# Choin_led1_0.net
KiCad netlist of a schematic drawn in Altium Designer
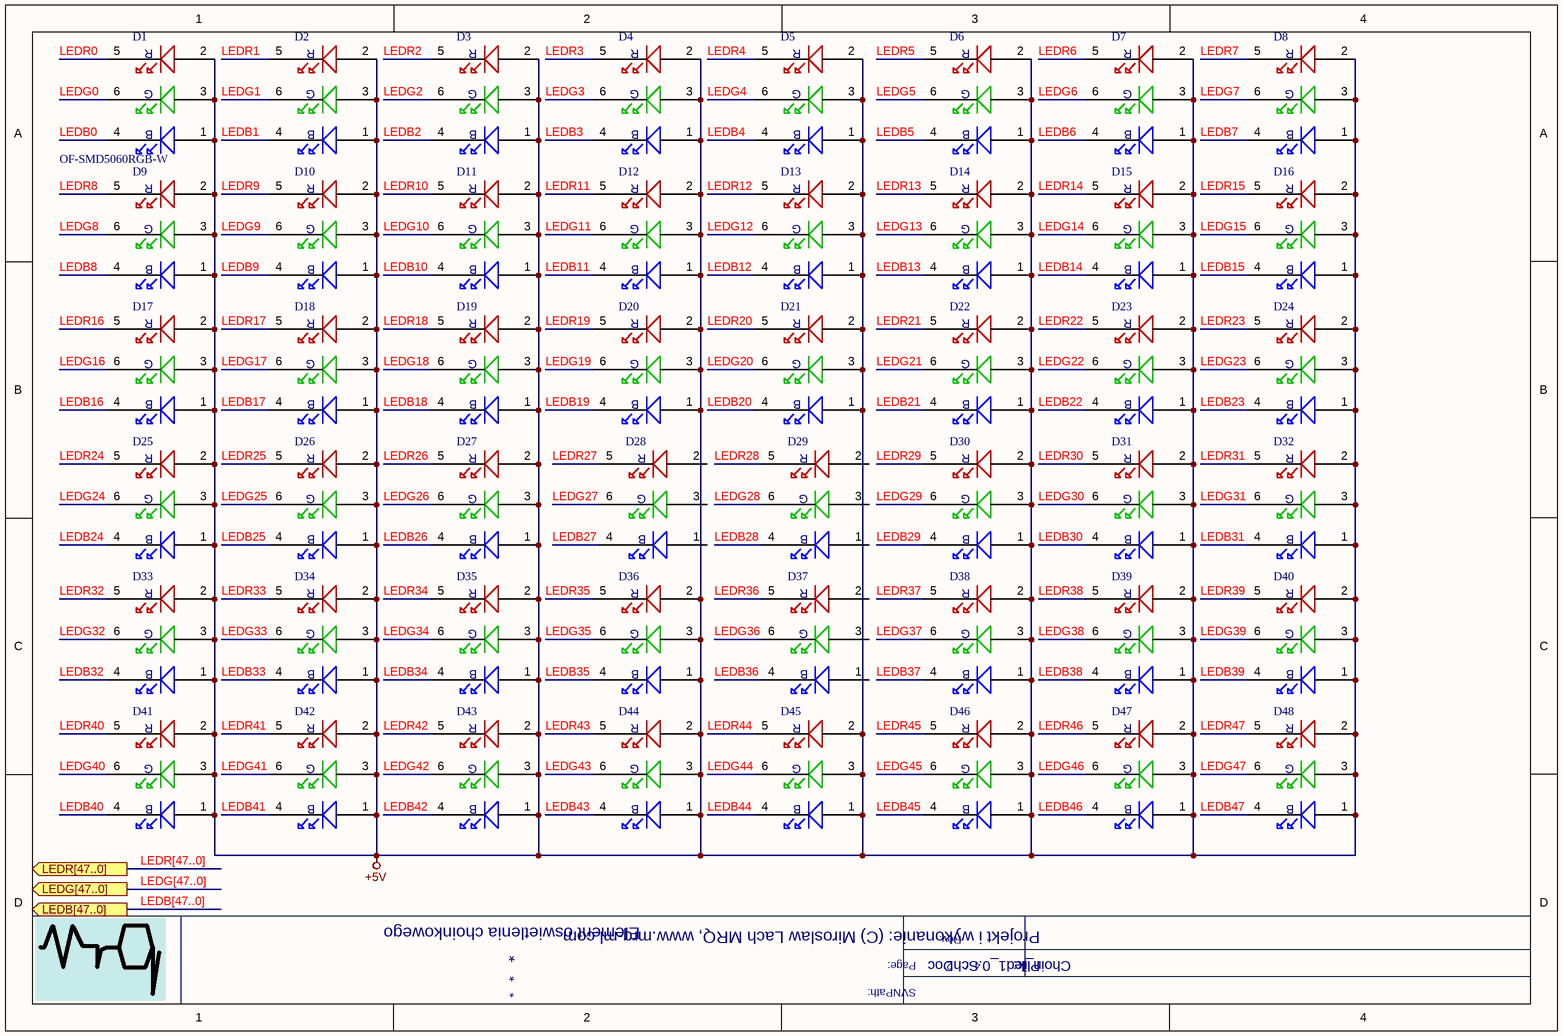
[diagram p0: Choin_led1_0.SchDoc]

(export (version "E")
  (design (tool "Eeschema 10.0.6"))
  (components
    (comp (ref "D1")
      (value "OF-SMD5060RGB-W")
      (footprint "OF-SMD5060RGB-W")
      (libsource (lib "Parts") (part "OF-SMD5060RGB-W"))
    )
    (comp (ref "D2")
      (value "OF-SMD5060RGB-W")
      (footprint "OF-SMD5060RGB-W")
      (libsource (lib "Parts") (part "OF-SMD5060RGB-W"))
    )
    (comp (ref "D3")
      (value "OF-SMD5060RGB-W")
      (footprint "OF-SMD5060RGB-W")
      (libsource (lib "Parts") (part "OF-SMD5060RGB-W"))
    )
    (comp (ref "D4")
      (value "OF-SMD5060RGB-W")
      (footprint "OF-SMD5060RGB-W")
      (libsource (lib "Parts") (part "OF-SMD5060RGB-W"))
    )
    (comp (ref "D5")
      (value "OF-SMD5060RGB-W")
      (footprint "OF-SMD5060RGB-W")
      (libsource (lib "Parts") (part "OF-SMD5060RGB-W"))
    )
    (comp (ref "D6")
      (value "OF-SMD5060RGB-W")
      (footprint "OF-SMD5060RGB-W")
      (libsource (lib "Parts") (part "OF-SMD5060RGB-W"))
    )
    (comp (ref "D7")
      (value "OF-SMD5060RGB-W")
      (footprint "OF-SMD5060RGB-W")
      (libsource (lib "Parts") (part "OF-SMD5060RGB-W"))
    )
    (comp (ref "D8")
      (value "OF-SMD5060RGB-W")
      (footprint "OF-SMD5060RGB-W")
      (libsource (lib "Parts") (part "OF-SMD5060RGB-W"))
    )
    (comp (ref "D9")
      (value "OF-SMD5060RGB-W")
      (footprint "OF-SMD5060RGB-W")
      (libsource (lib "Parts") (part "OF-SMD5060RGB-W"))
    )
    (comp (ref "D10")
      (value "OF-SMD5060RGB-W")
      (footprint "OF-SMD5060RGB-W")
      (libsource (lib "Parts") (part "OF-SMD5060RGB-W"))
    )
    (comp (ref "D11")
      (value "OF-SMD5060RGB-W")
      (footprint "OF-SMD5060RGB-W")
      (libsource (lib "Parts") (part "OF-SMD5060RGB-W"))
    )
    (comp (ref "D12")
      (value "OF-SMD5060RGB-W")
      (footprint "OF-SMD5060RGB-W")
      (libsource (lib "Parts") (part "OF-SMD5060RGB-W"))
    )
    (comp (ref "D13")
      (value "OF-SMD5060RGB-W")
      (footprint "OF-SMD5060RGB-W")
      (libsource (lib "Parts") (part "OF-SMD5060RGB-W"))
    )
    (comp (ref "D14")
      (value "OF-SMD5060RGB-W")
      (footprint "OF-SMD5060RGB-W")
      (libsource (lib "Parts") (part "OF-SMD5060RGB-W"))
    )
    (comp (ref "D15")
      (value "OF-SMD5060RGB-W")
      (footprint "OF-SMD5060RGB-W")
      (libsource (lib "Parts") (part "OF-SMD5060RGB-W"))
    )
    (comp (ref "D16")
      (value "OF-SMD5060RGB-W")
      (footprint "OF-SMD5060RGB-W")
      (libsource (lib "Parts") (part "OF-SMD5060RGB-W"))
    )
    (comp (ref "D17")
      (value "OF-SMD5060RGB-W")
      (footprint "OF-SMD5060RGB-W")
      (libsource (lib "Parts") (part "OF-SMD5060RGB-W"))
    )
    (comp (ref "D18")
      (value "OF-SMD5060RGB-W")
      (footprint "OF-SMD5060RGB-W")
      (libsource (lib "Parts") (part "OF-SMD5060RGB-W"))
    )
    (comp (ref "D19")
      (value "OF-SMD5060RGB-W")
      (footprint "OF-SMD5060RGB-W")
      (libsource (lib "Parts") (part "OF-SMD5060RGB-W"))
    )
    (comp (ref "D20")
      (value "OF-SMD5060RGB-W")
      (footprint "OF-SMD5060RGB-W")
      (libsource (lib "Parts") (part "OF-SMD5060RGB-W"))
    )
    (comp (ref "D21")
      (value "OF-SMD5060RGB-W")
      (footprint "OF-SMD5060RGB-W")
      (libsource (lib "Parts") (part "OF-SMD5060RGB-W"))
    )
    (comp (ref "D22")
      (value "OF-SMD5060RGB-W")
      (footprint "OF-SMD5060RGB-W")
      (libsource (lib "Parts") (part "OF-SMD5060RGB-W"))
    )
    (comp (ref "D23")
      (value "OF-SMD5060RGB-W")
      (footprint "OF-SMD5060RGB-W")
      (libsource (lib "Parts") (part "OF-SMD5060RGB-W"))
    )
    (comp (ref "D24")
      (value "OF-SMD5060RGB-W")
      (footprint "OF-SMD5060RGB-W")
      (libsource (lib "Parts") (part "OF-SMD5060RGB-W"))
    )
    (comp (ref "D25")
      (value "OF-SMD5060RGB-W")
      (footprint "OF-SMD5060RGB-W")
      (libsource (lib "Parts") (part "OF-SMD5060RGB-W"))
    )
    (comp (ref "D26")
      (value "OF-SMD5060RGB-W")
      (footprint "OF-SMD5060RGB-W")
      (libsource (lib "Parts") (part "OF-SMD5060RGB-W"))
    )
    (comp (ref "D27")
      (value "OF-SMD5060RGB-W")
      (footprint "OF-SMD5060RGB-W")
      (libsource (lib "Parts") (part "OF-SMD5060RGB-W"))
    )
    (comp (ref "D28")
      (value "OF-SMD5060RGB-W")
      (footprint "OF-SMD5060RGB-W")
      (libsource (lib "Parts") (part "OF-SMD5060RGB-W"))
    )
    (comp (ref "D29")
      (value "OF-SMD5060RGB-W")
      (footprint "OF-SMD5060RGB-W")
      (libsource (lib "Parts") (part "OF-SMD5060RGB-W"))
    )
    (comp (ref "D30")
      (value "OF-SMD5060RGB-W")
      (footprint "OF-SMD5060RGB-W")
      (libsource (lib "Parts") (part "OF-SMD5060RGB-W"))
    )
    (comp (ref "D31")
      (value "OF-SMD5060RGB-W")
      (footprint "OF-SMD5060RGB-W")
      (libsource (lib "Parts") (part "OF-SMD5060RGB-W"))
    )
    (comp (ref "D32")
      (value "OF-SMD5060RGB-W")
      (footprint "OF-SMD5060RGB-W")
      (libsource (lib "Parts") (part "OF-SMD5060RGB-W"))
    )
    (comp (ref "D33")
      (value "OF-SMD5060RGB-W")
      (footprint "OF-SMD5060RGB-W")
      (libsource (lib "Parts") (part "OF-SMD5060RGB-W"))
    )
    (comp (ref "D34")
      (value "OF-SMD5060RGB-W")
      (footprint "OF-SMD5060RGB-W")
      (libsource (lib "Parts") (part "OF-SMD5060RGB-W"))
    )
    (comp (ref "D35")
      (value "OF-SMD5060RGB-W")
      (footprint "OF-SMD5060RGB-W")
      (libsource (lib "Parts") (part "OF-SMD5060RGB-W"))
    )
    (comp (ref "D36")
      (value "OF-SMD5060RGB-W")
      (footprint "OF-SMD5060RGB-W")
      (libsource (lib "Parts") (part "OF-SMD5060RGB-W"))
    )
    (comp (ref "D37")
      (value "OF-SMD5060RGB-W")
      (footprint "OF-SMD5060RGB-W")
      (libsource (lib "Parts") (part "OF-SMD5060RGB-W"))
    )
    (comp (ref "D38")
      (value "OF-SMD5060RGB-W")
      (footprint "OF-SMD5060RGB-W")
      (libsource (lib "Parts") (part "OF-SMD5060RGB-W"))
    )
    (comp (ref "D39")
      (value "OF-SMD5060RGB-W")
      (footprint "OF-SMD5060RGB-W")
      (libsource (lib "Parts") (part "OF-SMD5060RGB-W"))
    )
    (comp (ref "D40")
      (value "OF-SMD5060RGB-W")
      (footprint "OF-SMD5060RGB-W")
      (libsource (lib "Parts") (part "OF-SMD5060RGB-W"))
    )
    (comp (ref "D41")
      (value "OF-SMD5060RGB-W")
      (footprint "OF-SMD5060RGB-W")
      (libsource (lib "Parts") (part "OF-SMD5060RGB-W"))
    )
    (comp (ref "D42")
      (value "OF-SMD5060RGB-W")
      (footprint "OF-SMD5060RGB-W")
      (libsource (lib "Parts") (part "OF-SMD5060RGB-W"))
    )
    (comp (ref "D43")
      (value "OF-SMD5060RGB-W")
      (footprint "OF-SMD5060RGB-W")
      (libsource (lib "Parts") (part "OF-SMD5060RGB-W"))
    )
    (comp (ref "D44")
      (value "OF-SMD5060RGB-W")
      (footprint "OF-SMD5060RGB-W")
      (libsource (lib "Parts") (part "OF-SMD5060RGB-W"))
    )
    (comp (ref "D45")
      (value "OF-SMD5060RGB-W")
      (footprint "OF-SMD5060RGB-W")
      (libsource (lib "Parts") (part "OF-SMD5060RGB-W"))
    )
    (comp (ref "D46")
      (value "OF-SMD5060RGB-W")
      (footprint "OF-SMD5060RGB-W")
      (libsource (lib "Parts") (part "OF-SMD5060RGB-W"))
    )
    (comp (ref "D47")
      (value "OF-SMD5060RGB-W")
      (footprint "OF-SMD5060RGB-W")
      (libsource (lib "Parts") (part "OF-SMD5060RGB-W"))
    )
    (comp (ref "D48")
      (value "OF-SMD5060RGB-W")
      (footprint "OF-SMD5060RGB-W")
      (libsource (lib "Parts") (part "OF-SMD5060RGB-W"))
    )
  )
  (nets
    (net (code "1") (name "+5V") (class "Default")
      (node (ref "D1") (pin "1") (pinfunction "ANOD_1") (pintype "passive"))
      (node (ref "D1") (pin "2") (pinfunction "ANOD_2") (pintype "passive"))
      (node (ref "D1") (pin "3") (pinfunction "ANOD_3") (pintype "passive"))
      (node (ref "D10") (pin "1") (pinfunction "ANOD_1") (pintype "passive"))
      (node (ref "D10") (pin "2") (pinfunction "ANOD_2") (pintype "passive"))
      (node (ref "D10") (pin "3") (pinfunction "ANOD_3") (pintype "passive"))
      (node (ref "D11") (pin "1") (pinfunction "ANOD_1") (pintype "passive"))
      (node (ref "D11") (pin "2") (pinfunction "ANOD_2") (pintype "passive"))
      (node (ref "D11") (pin "3") (pinfunction "ANOD_3") (pintype "passive"))
      (node (ref "D12") (pin "1") (pinfunction "ANOD_1") (pintype "passive"))
      (node (ref "D12") (pin "2") (pinfunction "ANOD_2") (pintype "passive"))
      (node (ref "D12") (pin "3") (pinfunction "ANOD_3") (pintype "passive"))
      (node (ref "D13") (pin "1") (pinfunction "ANOD_1") (pintype "passive"))
      (node (ref "D13") (pin "2") (pinfunction "ANOD_2") (pintype "passive"))
      (node (ref "D13") (pin "3") (pinfunction "ANOD_3") (pintype "passive"))
      (node (ref "D14") (pin "1") (pinfunction "ANOD_1") (pintype "passive"))
      (node (ref "D14") (pin "2") (pinfunction "ANOD_2") (pintype "passive"))
      (node (ref "D14") (pin "3") (pinfunction "ANOD_3") (pintype "passive"))
      (node (ref "D15") (pin "1") (pinfunction "ANOD_1") (pintype "passive"))
      (node (ref "D15") (pin "2") (pinfunction "ANOD_2") (pintype "passive"))
      (node (ref "D15") (pin "3") (pinfunction "ANOD_3") (pintype "passive"))
      (node (ref "D16") (pin "1") (pinfunction "ANOD_1") (pintype "passive"))
      (node (ref "D16") (pin "2") (pinfunction "ANOD_2") (pintype "passive"))
      (node (ref "D16") (pin "3") (pinfunction "ANOD_3") (pintype "passive"))
      (node (ref "D17") (pin "1") (pinfunction "ANOD_1") (pintype "passive"))
      (node (ref "D17") (pin "2") (pinfunction "ANOD_2") (pintype "passive"))
      (node (ref "D17") (pin "3") (pinfunction "ANOD_3") (pintype "passive"))
      (node (ref "D18") (pin "1") (pinfunction "ANOD_1") (pintype "passive"))
      (node (ref "D18") (pin "2") (pinfunction "ANOD_2") (pintype "passive"))
      (node (ref "D18") (pin "3") (pinfunction "ANOD_3") (pintype "passive"))
      (node (ref "D19") (pin "1") (pinfunction "ANOD_1") (pintype "passive"))
      (node (ref "D19") (pin "2") (pinfunction "ANOD_2") (pintype "passive"))
      (node (ref "D19") (pin "3") (pinfunction "ANOD_3") (pintype "passive"))
      (node (ref "D2") (pin "1") (pinfunction "ANOD_1") (pintype "passive"))
      (node (ref "D2") (pin "2") (pinfunction "ANOD_2") (pintype "passive"))
      (node (ref "D2") (pin "3") (pinfunction "ANOD_3") (pintype "passive"))
      (node (ref "D20") (pin "1") (pinfunction "ANOD_1") (pintype "passive"))
      (node (ref "D20") (pin "2") (pinfunction "ANOD_2") (pintype "passive"))
      (node (ref "D20") (pin "3") (pinfunction "ANOD_3") (pintype "passive"))
      (node (ref "D21") (pin "1") (pinfunction "ANOD_1") (pintype "passive"))
      (node (ref "D21") (pin "2") (pinfunction "ANOD_2") (pintype "passive"))
      (node (ref "D21") (pin "3") (pinfunction "ANOD_3") (pintype "passive"))
      (node (ref "D22") (pin "1") (pinfunction "ANOD_1") (pintype "passive"))
      (node (ref "D22") (pin "2") (pinfunction "ANOD_2") (pintype "passive"))
      (node (ref "D22") (pin "3") (pinfunction "ANOD_3") (pintype "passive"))
      (node (ref "D23") (pin "1") (pinfunction "ANOD_1") (pintype "passive"))
      (node (ref "D23") (pin "2") (pinfunction "ANOD_2") (pintype "passive"))
      (node (ref "D23") (pin "3") (pinfunction "ANOD_3") (pintype "passive"))
      (node (ref "D24") (pin "1") (pinfunction "ANOD_1") (pintype "passive"))
      (node (ref "D24") (pin "2") (pinfunction "ANOD_2") (pintype "passive"))
      (node (ref "D24") (pin "3") (pinfunction "ANOD_3") (pintype "passive"))
      (node (ref "D25") (pin "1") (pinfunction "ANOD_1") (pintype "passive"))
      (node (ref "D25") (pin "2") (pinfunction "ANOD_2") (pintype "passive"))
      (node (ref "D25") (pin "3") (pinfunction "ANOD_3") (pintype "passive"))
      (node (ref "D26") (pin "1") (pinfunction "ANOD_1") (pintype "passive"))
      (node (ref "D26") (pin "2") (pinfunction "ANOD_2") (pintype "passive"))
      (node (ref "D26") (pin "3") (pinfunction "ANOD_3") (pintype "passive"))
      (node (ref "D27") (pin "1") (pinfunction "ANOD_1") (pintype "passive"))
      (node (ref "D27") (pin "2") (pinfunction "ANOD_2") (pintype "passive"))
      (node (ref "D27") (pin "3") (pinfunction "ANOD_3") (pintype "passive"))
      (node (ref "D3") (pin "1") (pinfunction "ANOD_1") (pintype "passive"))
      (node (ref "D3") (pin "2") (pinfunction "ANOD_2") (pintype "passive"))
      (node (ref "D3") (pin "3") (pinfunction "ANOD_3") (pintype "passive"))
      (node (ref "D30") (pin "1") (pinfunction "ANOD_1") (pintype "passive"))
      (node (ref "D30") (pin "2") (pinfunction "ANOD_2") (pintype "passive"))
      (node (ref "D30") (pin "3") (pinfunction "ANOD_3") (pintype "passive"))
      (node (ref "D31") (pin "1") (pinfunction "ANOD_1") (pintype "passive"))
      (node (ref "D31") (pin "2") (pinfunction "ANOD_2") (pintype "passive"))
      (node (ref "D31") (pin "3") (pinfunction "ANOD_3") (pintype "passive"))
      (node (ref "D32") (pin "1") (pinfunction "ANOD_1") (pintype "passive"))
      (node (ref "D32") (pin "2") (pinfunction "ANOD_2") (pintype "passive"))
      (node (ref "D32") (pin "3") (pinfunction "ANOD_3") (pintype "passive"))
      (node (ref "D33") (pin "1") (pinfunction "ANOD_1") (pintype "passive"))
      (node (ref "D33") (pin "2") (pinfunction "ANOD_2") (pintype "passive"))
      (node (ref "D33") (pin "3") (pinfunction "ANOD_3") (pintype "passive"))
      (node (ref "D34") (pin "1") (pinfunction "ANOD_1") (pintype "passive"))
      (node (ref "D34") (pin "2") (pinfunction "ANOD_2") (pintype "passive"))
      (node (ref "D34") (pin "3") (pinfunction "ANOD_3") (pintype "passive"))
      (node (ref "D35") (pin "1") (pinfunction "ANOD_1") (pintype "passive"))
      (node (ref "D35") (pin "2") (pinfunction "ANOD_2") (pintype "passive"))
      (node (ref "D35") (pin "3") (pinfunction "ANOD_3") (pintype "passive"))
      (node (ref "D36") (pin "1") (pinfunction "ANOD_1") (pintype "passive"))
      (node (ref "D36") (pin "2") (pinfunction "ANOD_2") (pintype "passive"))
      (node (ref "D36") (pin "3") (pinfunction "ANOD_3") (pintype "passive"))
      (node (ref "D38") (pin "1") (pinfunction "ANOD_1") (pintype "passive"))
      (node (ref "D38") (pin "2") (pinfunction "ANOD_2") (pintype "passive"))
      (node (ref "D38") (pin "3") (pinfunction "ANOD_3") (pintype "passive"))
      (node (ref "D39") (pin "1") (pinfunction "ANOD_1") (pintype "passive"))
      (node (ref "D39") (pin "2") (pinfunction "ANOD_2") (pintype "passive"))
      (node (ref "D39") (pin "3") (pinfunction "ANOD_3") (pintype "passive"))
      (node (ref "D4") (pin "1") (pinfunction "ANOD_1") (pintype "passive"))
      (node (ref "D4") (pin "2") (pinfunction "ANOD_2") (pintype "passive"))
      (node (ref "D4") (pin "3") (pinfunction "ANOD_3") (pintype "passive"))
      (node (ref "D40") (pin "1") (pinfunction "ANOD_1") (pintype "passive"))
      (node (ref "D40") (pin "2") (pinfunction "ANOD_2") (pintype "passive"))
      (node (ref "D40") (pin "3") (pinfunction "ANOD_3") (pintype "passive"))
      (node (ref "D41") (pin "1") (pinfunction "ANOD_1") (pintype "passive"))
      (node (ref "D41") (pin "2") (pinfunction "ANOD_2") (pintype "passive"))
      (node (ref "D41") (pin "3") (pinfunction "ANOD_3") (pintype "passive"))
      (node (ref "D42") (pin "1") (pinfunction "ANOD_1") (pintype "passive"))
      (node (ref "D42") (pin "2") (pinfunction "ANOD_2") (pintype "passive"))
      (node (ref "D42") (pin "3") (pinfunction "ANOD_3") (pintype "passive"))
      (node (ref "D43") (pin "1") (pinfunction "ANOD_1") (pintype "passive"))
      (node (ref "D43") (pin "2") (pinfunction "ANOD_2") (pintype "passive"))
      (node (ref "D43") (pin "3") (pinfunction "ANOD_3") (pintype "passive"))
      (node (ref "D44") (pin "1") (pinfunction "ANOD_1") (pintype "passive"))
      (node (ref "D44") (pin "2") (pinfunction "ANOD_2") (pintype "passive"))
      (node (ref "D44") (pin "3") (pinfunction "ANOD_3") (pintype "passive"))
      (node (ref "D45") (pin "1") (pinfunction "ANOD_1") (pintype "passive"))
      (node (ref "D45") (pin "2") (pinfunction "ANOD_2") (pintype "passive"))
      (node (ref "D45") (pin "3") (pinfunction "ANOD_3") (pintype "passive"))
      (node (ref "D46") (pin "1") (pinfunction "ANOD_1") (pintype "passive"))
      (node (ref "D46") (pin "2") (pinfunction "ANOD_2") (pintype "passive"))
      (node (ref "D46") (pin "3") (pinfunction "ANOD_3") (pintype "passive"))
      (node (ref "D47") (pin "1") (pinfunction "ANOD_1") (pintype "passive"))
      (node (ref "D47") (pin "2") (pinfunction "ANOD_2") (pintype "passive"))
      (node (ref "D47") (pin "3") (pinfunction "ANOD_3") (pintype "passive"))
      (node (ref "D48") (pin "1") (pinfunction "ANOD_1") (pintype "passive"))
      (node (ref "D48") (pin "2") (pinfunction "ANOD_2") (pintype "passive"))
      (node (ref "D48") (pin "3") (pinfunction "ANOD_3") (pintype "passive"))
      (node (ref "D5") (pin "1") (pinfunction "ANOD_1") (pintype "passive"))
      (node (ref "D5") (pin "2") (pinfunction "ANOD_2") (pintype "passive"))
      (node (ref "D5") (pin "3") (pinfunction "ANOD_3") (pintype "passive"))
      (node (ref "D6") (pin "1") (pinfunction "ANOD_1") (pintype "passive"))
      (node (ref "D6") (pin "2") (pinfunction "ANOD_2") (pintype "passive"))
      (node (ref "D6") (pin "3") (pinfunction "ANOD_3") (pintype "passive"))
      (node (ref "D7") (pin "1") (pinfunction "ANOD_1") (pintype "passive"))
      (node (ref "D7") (pin "2") (pinfunction "ANOD_2") (pintype "passive"))
      (node (ref "D7") (pin "3") (pinfunction "ANOD_3") (pintype "passive"))
      (node (ref "D8") (pin "1") (pinfunction "ANOD_1") (pintype "passive"))
      (node (ref "D8") (pin "2") (pinfunction "ANOD_2") (pintype "passive"))
      (node (ref "D8") (pin "3") (pinfunction "ANOD_3") (pintype "passive"))
      (node (ref "D9") (pin "1") (pinfunction "ANOD_1") (pintype "passive"))
      (node (ref "D9") (pin "2") (pinfunction "ANOD_2") (pintype "passive"))
      (node (ref "D9") (pin "3") (pinfunction "ANOD_3") (pintype "passive"))
    )
    (net (code "2") (name "/LEDB0") (class "Default")
      (node (ref "D1") (pin "4") (pinfunction "CATH_4") (pintype "passive"))
    )
    (net (code "3") (name "/LEDB1") (class "Default")
      (node (ref "D2") (pin "4") (pinfunction "CATH_4") (pintype "passive"))
    )
    (net (code "4") (name "/LEDB2") (class "Default")
      (node (ref "D3") (pin "4") (pinfunction "CATH_4") (pintype "passive"))
    )
    (net (code "5") (name "/LEDB3") (class "Default")
      (node (ref "D4") (pin "4") (pinfunction "CATH_4") (pintype "passive"))
    )
    (net (code "6") (name "/LEDB4") (class "Default")
      (node (ref "D5") (pin "4") (pinfunction "CATH_4") (pintype "passive"))
    )
    (net (code "7") (name "/LEDB5") (class "Default")
      (node (ref "D6") (pin "4") (pinfunction "CATH_4") (pintype "passive"))
    )
    (net (code "8") (name "/LEDB6") (class "Default")
      (node (ref "D7") (pin "4") (pinfunction "CATH_4") (pintype "passive"))
    )
    (net (code "9") (name "/LEDB7") (class "Default")
      (node (ref "D8") (pin "4") (pinfunction "CATH_4") (pintype "passive"))
    )
    (net (code "10") (name "/LEDB8") (class "Default")
      (node (ref "D9") (pin "4") (pinfunction "CATH_4") (pintype "passive"))
    )
    (net (code "11") (name "/LEDB9") (class "Default")
      (node (ref "D10") (pin "4") (pinfunction "CATH_4") (pintype "passive"))
    )
    (net (code "12") (name "/LEDB10") (class "Default")
      (node (ref "D11") (pin "4") (pinfunction "CATH_4") (pintype "passive"))
    )
    (net (code "13") (name "/LEDB11") (class "Default")
      (node (ref "D12") (pin "4") (pinfunction "CATH_4") (pintype "passive"))
    )
    (net (code "14") (name "/LEDB12") (class "Default")
      (node (ref "D13") (pin "4") (pinfunction "CATH_4") (pintype "passive"))
    )
    (net (code "15") (name "/LEDB13") (class "Default")
      (node (ref "D14") (pin "4") (pinfunction "CATH_4") (pintype "passive"))
    )
    (net (code "16") (name "/LEDB14") (class "Default")
      (node (ref "D15") (pin "4") (pinfunction "CATH_4") (pintype "passive"))
    )
    (net (code "17") (name "/LEDB15") (class "Default")
      (node (ref "D16") (pin "4") (pinfunction "CATH_4") (pintype "passive"))
    )
    (net (code "18") (name "/LEDB16") (class "Default")
      (node (ref "D17") (pin "4") (pinfunction "CATH_4") (pintype "passive"))
    )
    (net (code "19") (name "/LEDB17") (class "Default")
      (node (ref "D18") (pin "4") (pinfunction "CATH_4") (pintype "passive"))
    )
    (net (code "20") (name "/LEDB18") (class "Default")
      (node (ref "D19") (pin "4") (pinfunction "CATH_4") (pintype "passive"))
    )
    (net (code "21") (name "/LEDB19") (class "Default")
      (node (ref "D20") (pin "4") (pinfunction "CATH_4") (pintype "passive"))
    )
    (net (code "22") (name "/LEDB20") (class "Default")
      (node (ref "D21") (pin "4") (pinfunction "CATH_4") (pintype "passive"))
    )
    (net (code "23") (name "/LEDB21") (class "Default")
      (node (ref "D22") (pin "4") (pinfunction "CATH_4") (pintype "passive"))
    )
    (net (code "24") (name "/LEDB22") (class "Default")
      (node (ref "D23") (pin "4") (pinfunction "CATH_4") (pintype "passive"))
    )
    (net (code "25") (name "/LEDB23") (class "Default")
      (node (ref "D24") (pin "4") (pinfunction "CATH_4") (pintype "passive"))
    )
    (net (code "26") (name "/LEDB24") (class "Default")
      (node (ref "D25") (pin "4") (pinfunction "CATH_4") (pintype "passive"))
    )
    (net (code "27") (name "/LEDB25") (class "Default")
      (node (ref "D26") (pin "4") (pinfunction "CATH_4") (pintype "passive"))
    )
    (net (code "28") (name "/LEDB26") (class "Default")
      (node (ref "D27") (pin "4") (pinfunction "CATH_4") (pintype "passive"))
    )
    (net (code "29") (name "/LEDB27") (class "Default")
      (node (ref "D28") (pin "4") (pinfunction "CATH_4") (pintype "passive"))
    )
    (net (code "30") (name "/LEDB28") (class "Default")
      (node (ref "D29") (pin "4") (pinfunction "CATH_4") (pintype "passive"))
    )
    (net (code "31") (name "/LEDB29") (class "Default")
      (node (ref "D30") (pin "4") (pinfunction "CATH_4") (pintype "passive"))
    )
    (net (code "32") (name "/LEDB30") (class "Default")
      (node (ref "D31") (pin "4") (pinfunction "CATH_4") (pintype "passive"))
    )
    (net (code "33") (name "/LEDB31") (class "Default")
      (node (ref "D32") (pin "4") (pinfunction "CATH_4") (pintype "passive"))
    )
    (net (code "34") (name "/LEDB32") (class "Default")
      (node (ref "D33") (pin "4") (pinfunction "CATH_4") (pintype "passive"))
    )
    (net (code "35") (name "/LEDB33") (class "Default")
      (node (ref "D34") (pin "4") (pinfunction "CATH_4") (pintype "passive"))
    )
    (net (code "36") (name "/LEDB34") (class "Default")
      (node (ref "D35") (pin "4") (pinfunction "CATH_4") (pintype "passive"))
    )
    (net (code "37") (name "/LEDB35") (class "Default")
      (node (ref "D36") (pin "4") (pinfunction "CATH_4") (pintype "passive"))
    )
    (net (code "38") (name "/LEDB36") (class "Default")
      (node (ref "D37") (pin "4") (pinfunction "CATH_4") (pintype "passive"))
    )
    (net (code "39") (name "/LEDB37") (class "Default")
      (node (ref "D38") (pin "4") (pinfunction "CATH_4") (pintype "passive"))
    )
    (net (code "40") (name "/LEDB38") (class "Default")
      (node (ref "D39") (pin "4") (pinfunction "CATH_4") (pintype "passive"))
    )
    (net (code "41") (name "/LEDB39") (class "Default")
      (node (ref "D40") (pin "4") (pinfunction "CATH_4") (pintype "passive"))
    )
    (net (code "42") (name "/LEDB40") (class "Default")
      (node (ref "D41") (pin "4") (pinfunction "CATH_4") (pintype "passive"))
    )
    (net (code "43") (name "/LEDB41") (class "Default")
      (node (ref "D42") (pin "4") (pinfunction "CATH_4") (pintype "passive"))
    )
    (net (code "44") (name "/LEDB42") (class "Default")
      (node (ref "D43") (pin "4") (pinfunction "CATH_4") (pintype "passive"))
    )
    (net (code "45") (name "/LEDB43") (class "Default")
      (node (ref "D44") (pin "4") (pinfunction "CATH_4") (pintype "passive"))
    )
    (net (code "46") (name "/LEDB44") (class "Default")
      (node (ref "D45") (pin "4") (pinfunction "CATH_4") (pintype "passive"))
    )
    (net (code "47") (name "/LEDB45") (class "Default")
      (node (ref "D46") (pin "4") (pinfunction "CATH_4") (pintype "passive"))
    )
    (net (code "48") (name "/LEDB46") (class "Default")
      (node (ref "D47") (pin "4") (pinfunction "CATH_4") (pintype "passive"))
    )
    (net (code "49") (name "/LEDB47") (class "Default")
      (node (ref "D48") (pin "4") (pinfunction "CATH_4") (pintype "passive"))
    )
    (net (code "51") (name "/LEDG0") (class "Default")
      (node (ref "D1") (pin "6") (pinfunction "CATH_6") (pintype "passive"))
    )
    (net (code "52") (name "/LEDG1") (class "Default")
      (node (ref "D2") (pin "6") (pinfunction "CATH_6") (pintype "passive"))
    )
    (net (code "53") (name "/LEDG2") (class "Default")
      (node (ref "D3") (pin "6") (pinfunction "CATH_6") (pintype "passive"))
    )
    (net (code "54") (name "/LEDG3") (class "Default")
      (node (ref "D4") (pin "6") (pinfunction "CATH_6") (pintype "passive"))
    )
    (net (code "55") (name "/LEDG4") (class "Default")
      (node (ref "D5") (pin "6") (pinfunction "CATH_6") (pintype "passive"))
    )
    (net (code "56") (name "/LEDG5") (class "Default")
      (node (ref "D6") (pin "6") (pinfunction "CATH_6") (pintype "passive"))
    )
    (net (code "57") (name "/LEDG6") (class "Default")
      (node (ref "D7") (pin "6") (pinfunction "CATH_6") (pintype "passive"))
    )
    (net (code "58") (name "/LEDG7") (class "Default")
      (node (ref "D8") (pin "6") (pinfunction "CATH_6") (pintype "passive"))
    )
    (net (code "59") (name "/LEDG8") (class "Default")
      (node (ref "D9") (pin "6") (pinfunction "CATH_6") (pintype "passive"))
    )
    (net (code "60") (name "/LEDG9") (class "Default")
      (node (ref "D10") (pin "6") (pinfunction "CATH_6") (pintype "passive"))
    )
    (net (code "61") (name "/LEDG10") (class "Default")
      (node (ref "D11") (pin "6") (pinfunction "CATH_6") (pintype "passive"))
    )
    (net (code "62") (name "/LEDG11") (class "Default")
      (node (ref "D12") (pin "6") (pinfunction "CATH_6") (pintype "passive"))
    )
    (net (code "63") (name "/LEDG12") (class "Default")
      (node (ref "D13") (pin "6") (pinfunction "CATH_6") (pintype "passive"))
    )
    (net (code "64") (name "/LEDG13") (class "Default")
      (node (ref "D14") (pin "6") (pinfunction "CATH_6") (pintype "passive"))
    )
    (net (code "65") (name "/LEDG14") (class "Default")
      (node (ref "D15") (pin "6") (pinfunction "CATH_6") (pintype "passive"))
    )
    (net (code "66") (name "/LEDG15") (class "Default")
      (node (ref "D16") (pin "6") (pinfunction "CATH_6") (pintype "passive"))
    )
    (net (code "67") (name "/LEDG16") (class "Default")
      (node (ref "D17") (pin "6") (pinfunction "CATH_6") (pintype "passive"))
    )
    (net (code "68") (name "/LEDG17") (class "Default")
      (node (ref "D18") (pin "6") (pinfunction "CATH_6") (pintype "passive"))
    )
    (net (code "69") (name "/LEDG18") (class "Default")
      (node (ref "D19") (pin "6") (pinfunction "CATH_6") (pintype "passive"))
    )
    (net (code "70") (name "/LEDG19") (class "Default")
      (node (ref "D20") (pin "6") (pinfunction "CATH_6") (pintype "passive"))
    )
    (net (code "71") (name "/LEDG20") (class "Default")
      (node (ref "D21") (pin "6") (pinfunction "CATH_6") (pintype "passive"))
    )
    (net (code "72") (name "/LEDG21") (class "Default")
      (node (ref "D22") (pin "6") (pinfunction "CATH_6") (pintype "passive"))
    )
    (net (code "73") (name "/LEDG22") (class "Default")
      (node (ref "D23") (pin "6") (pinfunction "CATH_6") (pintype "passive"))
    )
    (net (code "74") (name "/LEDG23") (class "Default")
      (node (ref "D24") (pin "6") (pinfunction "CATH_6") (pintype "passive"))
    )
    (net (code "75") (name "/LEDG24") (class "Default")
      (node (ref "D25") (pin "6") (pinfunction "CATH_6") (pintype "passive"))
    )
    (net (code "76") (name "/LEDG25") (class "Default")
      (node (ref "D26") (pin "6") (pinfunction "CATH_6") (pintype "passive"))
    )
    (net (code "77") (name "/LEDG26") (class "Default")
      (node (ref "D27") (pin "6") (pinfunction "CATH_6") (pintype "passive"))
    )
    (net (code "78") (name "/LEDG27") (class "Default")
      (node (ref "D28") (pin "6") (pinfunction "CATH_6") (pintype "passive"))
    )
    (net (code "79") (name "/LEDG28") (class "Default")
      (node (ref "D29") (pin "6") (pinfunction "CATH_6") (pintype "passive"))
    )
    (net (code "80") (name "/LEDG29") (class "Default")
      (node (ref "D30") (pin "6") (pinfunction "CATH_6") (pintype "passive"))
    )
    (net (code "81") (name "/LEDG30") (class "Default")
      (node (ref "D31") (pin "6") (pinfunction "CATH_6") (pintype "passive"))
    )
    (net (code "82") (name "/LEDG31") (class "Default")
      (node (ref "D32") (pin "6") (pinfunction "CATH_6") (pintype "passive"))
    )
    (net (code "83") (name "/LEDG32") (class "Default")
      (node (ref "D33") (pin "6") (pinfunction "CATH_6") (pintype "passive"))
    )
    (net (code "84") (name "/LEDG33") (class "Default")
      (node (ref "D34") (pin "6") (pinfunction "CATH_6") (pintype "passive"))
    )
    (net (code "85") (name "/LEDG34") (class "Default")
      (node (ref "D35") (pin "6") (pinfunction "CATH_6") (pintype "passive"))
    )
    (net (code "86") (name "/LEDG35") (class "Default")
      (node (ref "D36") (pin "6") (pinfunction "CATH_6") (pintype "passive"))
    )
    (net (code "87") (name "/LEDG36") (class "Default")
      (node (ref "D37") (pin "6") (pinfunction "CATH_6") (pintype "passive"))
    )
    (net (code "88") (name "/LEDG37") (class "Default")
      (node (ref "D38") (pin "6") (pinfunction "CATH_6") (pintype "passive"))
    )
    (net (code "89") (name "/LEDG38") (class "Default")
      (node (ref "D39") (pin "6") (pinfunction "CATH_6") (pintype "passive"))
    )
    (net (code "90") (name "/LEDG39") (class "Default")
      (node (ref "D40") (pin "6") (pinfunction "CATH_6") (pintype "passive"))
    )
    (net (code "91") (name "/LEDG40") (class "Default")
      (node (ref "D41") (pin "6") (pinfunction "CATH_6") (pintype "passive"))
    )
    (net (code "92") (name "/LEDG41") (class "Default")
      (node (ref "D42") (pin "6") (pinfunction "CATH_6") (pintype "passive"))
    )
    (net (code "93") (name "/LEDG42") (class "Default")
      (node (ref "D43") (pin "6") (pinfunction "CATH_6") (pintype "passive"))
    )
    (net (code "94") (name "/LEDG43") (class "Default")
      (node (ref "D44") (pin "6") (pinfunction "CATH_6") (pintype "passive"))
    )
    (net (code "95") (name "/LEDG44") (class "Default")
      (node (ref "D45") (pin "6") (pinfunction "CATH_6") (pintype "passive"))
    )
    (net (code "96") (name "/LEDG45") (class "Default")
      (node (ref "D46") (pin "6") (pinfunction "CATH_6") (pintype "passive"))
    )
    (net (code "97") (name "/LEDG46") (class "Default")
      (node (ref "D47") (pin "6") (pinfunction "CATH_6") (pintype "passive"))
    )
    (net (code "98") (name "/LEDG47") (class "Default")
      (node (ref "D48") (pin "6") (pinfunction "CATH_6") (pintype "passive"))
    )
    (net (code "100") (name "/LEDR0") (class "Default")
      (node (ref "D1") (pin "5") (pinfunction "CATH_5") (pintype "passive"))
    )
    (net (code "101") (name "/LEDR1") (class "Default")
      (node (ref "D2") (pin "5") (pinfunction "CATH_5") (pintype "passive"))
    )
    (net (code "102") (name "/LEDR2") (class "Default")
      (node (ref "D3") (pin "5") (pinfunction "CATH_5") (pintype "passive"))
    )
    (net (code "103") (name "/LEDR3") (class "Default")
      (node (ref "D4") (pin "5") (pinfunction "CATH_5") (pintype "passive"))
    )
    (net (code "104") (name "/LEDR4") (class "Default")
      (node (ref "D5") (pin "5") (pinfunction "CATH_5") (pintype "passive"))
    )
    (net (code "105") (name "/LEDR5") (class "Default")
      (node (ref "D6") (pin "5") (pinfunction "CATH_5") (pintype "passive"))
    )
    (net (code "106") (name "/LEDR6") (class "Default")
      (node (ref "D7") (pin "5") (pinfunction "CATH_5") (pintype "passive"))
    )
    (net (code "107") (name "/LEDR7") (class "Default")
      (node (ref "D8") (pin "5") (pinfunction "CATH_5") (pintype "passive"))
    )
    (net (code "108") (name "/LEDR8") (class "Default")
      (node (ref "D9") (pin "5") (pinfunction "CATH_5") (pintype "passive"))
    )
    (net (code "109") (name "/LEDR9") (class "Default")
      (node (ref "D10") (pin "5") (pinfunction "CATH_5") (pintype "passive"))
    )
    (net (code "110") (name "/LEDR10") (class "Default")
      (node (ref "D11") (pin "5") (pinfunction "CATH_5") (pintype "passive"))
    )
    (net (code "111") (name "/LEDR11") (class "Default")
      (node (ref "D12") (pin "5") (pinfunction "CATH_5") (pintype "passive"))
    )
    (net (code "112") (name "/LEDR12") (class "Default")
      (node (ref "D13") (pin "5") (pinfunction "CATH_5") (pintype "passive"))
    )
    (net (code "113") (name "/LEDR13") (class "Default")
      (node (ref "D14") (pin "5") (pinfunction "CATH_5") (pintype "passive"))
    )
    (net (code "114") (name "/LEDR14") (class "Default")
      (node (ref "D15") (pin "5") (pinfunction "CATH_5") (pintype "passive"))
    )
    (net (code "115") (name "/LEDR15") (class "Default")
      (node (ref "D16") (pin "5") (pinfunction "CATH_5") (pintype "passive"))
    )
    (net (code "116") (name "/LEDR16") (class "Default")
      (node (ref "D17") (pin "5") (pinfunction "CATH_5") (pintype "passive"))
    )
    (net (code "117") (name "/LEDR17") (class "Default")
      (node (ref "D18") (pin "5") (pinfunction "CATH_5") (pintype "passive"))
    )
    (net (code "118") (name "/LEDR18") (class "Default")
      (node (ref "D19") (pin "5") (pinfunction "CATH_5") (pintype "passive"))
    )
    (net (code "119") (name "/LEDR19") (class "Default")
      (node (ref "D20") (pin "5") (pinfunction "CATH_5") (pintype "passive"))
    )
    (net (code "120") (name "/LEDR20") (class "Default")
      (node (ref "D21") (pin "5") (pinfunction "CATH_5") (pintype "passive"))
    )
    (net (code "121") (name "/LEDR21") (class "Default")
      (node (ref "D22") (pin "5") (pinfunction "CATH_5") (pintype "passive"))
    )
    (net (code "122") (name "/LEDR22") (class "Default")
      (node (ref "D23") (pin "5") (pinfunction "CATH_5") (pintype "passive"))
    )
    (net (code "123") (name "/LEDR23") (class "Default")
      (node (ref "D24") (pin "5") (pinfunction "CATH_5") (pintype "passive"))
    )
    (net (code "124") (name "/LEDR24") (class "Default")
      (node (ref "D25") (pin "5") (pinfunction "CATH_5") (pintype "passive"))
    )
    (net (code "125") (name "/LEDR25") (class "Default")
      (node (ref "D26") (pin "5") (pinfunction "CATH_5") (pintype "passive"))
    )
    (net (code "126") (name "/LEDR26") (class "Default")
      (node (ref "D27") (pin "5") (pinfunction "CATH_5") (pintype "passive"))
    )
    (net (code "127") (name "/LEDR27") (class "Default")
      (node (ref "D28") (pin "5") (pinfunction "CATH_5") (pintype "passive"))
    )
    (net (code "128") (name "/LEDR28") (class "Default")
      (node (ref "D29") (pin "5") (pinfunction "CATH_5") (pintype "passive"))
    )
    (net (code "129") (name "/LEDR29") (class "Default")
      (node (ref "D30") (pin "5") (pinfunction "CATH_5") (pintype "passive"))
    )
    (net (code "130") (name "/LEDR30") (class "Default")
      (node (ref "D31") (pin "5") (pinfunction "CATH_5") (pintype "passive"))
    )
    (net (code "131") (name "/LEDR31") (class "Default")
      (node (ref "D32") (pin "5") (pinfunction "CATH_5") (pintype "passive"))
    )
    (net (code "132") (name "/LEDR32") (class "Default")
      (node (ref "D33") (pin "5") (pinfunction "CATH_5") (pintype "passive"))
    )
    (net (code "133") (name "/LEDR33") (class "Default")
      (node (ref "D34") (pin "5") (pinfunction "CATH_5") (pintype "passive"))
    )
    (net (code "134") (name "/LEDR34") (class "Default")
      (node (ref "D35") (pin "5") (pinfunction "CATH_5") (pintype "passive"))
    )
    (net (code "135") (name "/LEDR35") (class "Default")
      (node (ref "D36") (pin "5") (pinfunction "CATH_5") (pintype "passive"))
    )
    (net (code "136") (name "/LEDR36") (class "Default")
      (node (ref "D37") (pin "5") (pinfunction "CATH_5") (pintype "passive"))
    )
    (net (code "137") (name "/LEDR37") (class "Default")
      (node (ref "D38") (pin "5") (pinfunction "CATH_5") (pintype "passive"))
    )
    (net (code "138") (name "/LEDR38") (class "Default")
      (node (ref "D39") (pin "5") (pinfunction "CATH_5") (pintype "passive"))
    )
    (net (code "139") (name "/LEDR39") (class "Default")
      (node (ref "D40") (pin "5") (pinfunction "CATH_5") (pintype "passive"))
    )
    (net (code "140") (name "/LEDR40") (class "Default")
      (node (ref "D41") (pin "5") (pinfunction "CATH_5") (pintype "passive"))
    )
    (net (code "141") (name "/LEDR41") (class "Default")
      (node (ref "D42") (pin "5") (pinfunction "CATH_5") (pintype "passive"))
    )
    (net (code "142") (name "/LEDR42") (class "Default")
      (node (ref "D43") (pin "5") (pinfunction "CATH_5") (pintype "passive"))
    )
    (net (code "143") (name "/LEDR43") (class "Default")
      (node (ref "D44") (pin "5") (pinfunction "CATH_5") (pintype "passive"))
    )
    (net (code "144") (name "/LEDR44") (class "Default")
      (node (ref "D45") (pin "5") (pinfunction "CATH_5") (pintype "passive"))
    )
    (net (code "145") (name "/LEDR45") (class "Default")
      (node (ref "D46") (pin "5") (pinfunction "CATH_5") (pintype "passive"))
    )
    (net (code "146") (name "/LEDR46") (class "Default")
      (node (ref "D47") (pin "5") (pinfunction "CATH_5") (pintype "passive"))
    )
    (net (code "147") (name "/LEDR47") (class "Default")
      (node (ref "D48") (pin "5") (pinfunction "CATH_5") (pintype "passive"))
    )
    (net (code "149") (name "unconnected-(D28-ANOD-Pad1)") (class "Default")
      (node (ref "D28") (pin "1") (pinfunction "ANOD_1") (pintype "passive"))
    )
    (net (code "150") (name "unconnected-(D28-ANOD-Pad2)") (class "Default")
      (node (ref "D28") (pin "2") (pinfunction "ANOD_2") (pintype "passive"))
    )
    (net (code "151") (name "unconnected-(D28-ANOD-Pad3)") (class "Default")
      (node (ref "D28") (pin "3") (pinfunction "ANOD_3") (pintype "passive"))
    )
    (net (code "152") (name "unconnected-(D29-ANOD-Pad1)") (class "Default")
      (node (ref "D29") (pin "1") (pinfunction "ANOD_1") (pintype "passive"))
    )
    (net (code "153") (name "unconnected-(D29-ANOD-Pad2)") (class "Default")
      (node (ref "D29") (pin "2") (pinfunction "ANOD_2") (pintype "passive"))
    )
    (net (code "154") (name "unconnected-(D29-ANOD-Pad3)") (class "Default")
      (node (ref "D29") (pin "3") (pinfunction "ANOD_3") (pintype "passive"))
    )
    (net (code "155") (name "unconnected-(D37-ANOD-Pad1)") (class "Default")
      (node (ref "D37") (pin "1") (pinfunction "ANOD_1") (pintype "passive"))
    )
    (net (code "156") (name "unconnected-(D37-ANOD-Pad2)") (class "Default")
      (node (ref "D37") (pin "2") (pinfunction "ANOD_2") (pintype "passive"))
    )
    (net (code "157") (name "unconnected-(D37-ANOD-Pad3)") (class "Default")
      (node (ref "D37") (pin "3") (pinfunction "ANOD_3") (pintype "passive"))
    )
  )
)
